# PAM8403_Amplifier_Board_R1.net
KiCad netlist of a schematic drawn in EAGLE
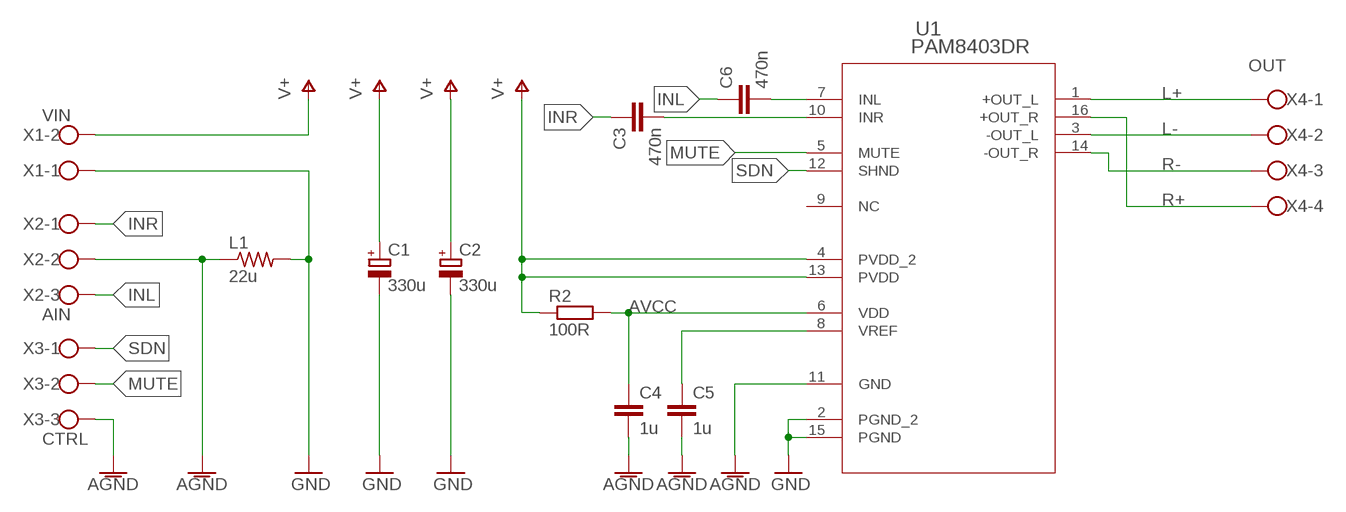
[diagram p0: schematic, sheet 1]

(export (version "E")
  (design (tool "Eeschema 10.0.6"))
  (components
    (comp (ref "C1")
      (value "330u")
      (footprint "eagle-import:E3,5-8")
      (libsource (lib "eagle-import") (part "CPOL-EUE3.5-8"))
    )
    (comp (ref "C2")
      (value "330u")
      (footprint "eagle-import:E3,5-8")
      (libsource (lib "eagle-import") (part "CPOL-EUE3.5-8"))
    )
    (comp (ref "C3")
      (value "470n")
      (footprint "eagle-import:C1206")
      (libsource (lib "eagle-import") (part "C-EUC1206"))
    )
    (comp (ref "C4")
      (value "1u")
      (footprint "eagle-import:C1206")
      (libsource (lib "eagle-import") (part "C-EUC1206"))
    )
    (comp (ref "C5")
      (value "1u")
      (footprint "eagle-import:C1206")
      (libsource (lib "eagle-import") (part "C-EUC1206"))
    )
    (comp (ref "C6")
      (value "470n")
      (footprint "eagle-import:C1206")
      (libsource (lib "eagle-import") (part "C-EUC1206"))
    )
    (comp (ref "L1")
      (value "22u")
      (footprint "eagle-import:R0805")
      (libsource (lib "eagle-import") (part "R-US_R0805"))
    )
    (comp (ref "R2")
      (value "100R")
      (footprint "eagle-import:R0603")
      (libsource (lib "eagle-import") (part "R-EU_R0603"))
    )
    (comp (ref "U1")
      (value "PAM8403DR")
      (footprint "eagle-import:SOIC_8403DR_DIO")
      (fields (field (name "COPYRIGHT") "Copyright (C) 2023 Ultra Librarian. All rights reserved."))
      (libsource (lib "eagle-import") (part "PAM8403DR"))
    )
    (comp (ref "X1")
      (value "VIN")
      (footprint "eagle-import:W237-102")
      (fields (field (name "MPN") "237-102"))
      (libsource (lib "eagle-import") (part "W237-102"))
    )
    (comp (ref "X2")
      (value "AIN")
      (footprint "eagle-import:W237-103")
      (fields (field (name "MPN") "237-103"))
      (libsource (lib "eagle-import") (part "W237-103"))
    )
    (comp (ref "X3")
      (value "CTRL")
      (footprint "eagle-import:W237-103")
      (fields (field (name "MPN") "237-103"))
      (libsource (lib "eagle-import") (part "W237-103"))
    )
    (comp (ref "X4")
      (value "OUT")
      (footprint "eagle-import:W237-4")
      (libsource (lib "eagle-import") (part "W237-4"))
    )
  )
  (nets
    (net (code "1") (name "/AVCC") (class "Default")
      (node (ref "C4") (pin "1") (pinfunction "1_1") (pintype "passive"))
      (node (ref "R2") (pin "2") (pinfunction "2_2") (pintype "passive"))
      (node (ref "U1") (pin "6") (pinfunction "VDD_6") (pintype "power_in"))
    )
    (net (code "2") (name "/L+") (class "Default")
      (node (ref "U1") (pin "1") (pinfunction "+OUT_L_1") (pintype "output"))
      (node (ref "X4") (pin "1") (pinfunction "KL_1") (pintype "passive"))
    )
    (net (code "3") (name "/L-") (class "Default")
      (node (ref "U1") (pin "3") (pinfunction "-OUT_L_3") (pintype "output"))
      (node (ref "X4") (pin "2") (pinfunction "KL_2") (pintype "passive"))
    )
    (net (code "4") (name "/R+") (class "Default")
      (node (ref "U1") (pin "16") (pinfunction "+OUT_R_16") (pintype "output"))
      (node (ref "X4") (pin "4") (pinfunction "KL_4") (pintype "passive"))
    )
    (net (code "5") (name "/R-") (class "Default")
      (node (ref "U1") (pin "14") (pinfunction "-OUT_R_14") (pintype "output"))
      (node (ref "X4") (pin "3") (pinfunction "KL_3") (pintype "passive"))
    )
    (net (code "6") (name "AGND") (class "Default")
      (node (ref "C4") (pin "2") (pinfunction "2_2") (pintype "passive"))
      (node (ref "C5") (pin "2") (pinfunction "2_2") (pintype "passive"))
      (node (ref "L1") (pin "1") (pinfunction "1_1") (pintype "passive"))
      (node (ref "U1") (pin "11") (pinfunction "GND_11") (pintype "passive"))
      (node (ref "X2") (pin "2") (pinfunction "KL_2") (pintype "passive"))
      (node (ref "X3") (pin "3") (pinfunction "KL_3") (pintype "passive"))
    )
    (net (code "7") (name "GND") (class "Default")
      (node (ref "C1") (pin "-") (pinfunction "-_-") (pintype "passive"))
      (node (ref "C2") (pin "-") (pinfunction "-_-") (pintype "passive"))
      (node (ref "L1") (pin "2") (pinfunction "2_2") (pintype "passive"))
      (node (ref "U1") (pin "15") (pinfunction "PGND_15") (pintype "passive"))
      (node (ref "U1") (pin "2") (pinfunction "PGND_2_2") (pintype "passive"))
      (node (ref "X1") (pin "1") (pinfunction "KL_1") (pintype "passive"))
    )
    (net (code "8") (name "INL") (class "Default")
      (node (ref "C6") (pin "1") (pinfunction "1_1") (pintype "passive"))
      (node (ref "X2") (pin "3") (pinfunction "KL_3") (pintype "passive"))
    )
    (net (code "9") (name "INR") (class "Default")
      (node (ref "C3") (pin "1") (pinfunction "1_1") (pintype "passive"))
      (node (ref "X2") (pin "1") (pinfunction "KL_1") (pintype "passive"))
    )
    (net (code "10") (name "MUTE") (class "Default")
      (node (ref "U1") (pin "5") (pinfunction "MUTE_5") (pintype "passive"))
      (node (ref "X3") (pin "2") (pinfunction "KL_2") (pintype "passive"))
    )
    (net (code "11") (name "Net-(U1-INL)") (class "Default")
      (node (ref "C6") (pin "2") (pinfunction "2_2") (pintype "passive"))
      (node (ref "U1") (pin "7") (pinfunction "INL_7") (pintype "passive"))
    )
    (net (code "12") (name "Net-(U1-INR)") (class "Default")
      (node (ref "C3") (pin "2") (pinfunction "2_2") (pintype "passive"))
      (node (ref "U1") (pin "10") (pinfunction "INR_10") (pintype "passive"))
    )
    (net (code "13") (name "Net-(U1-VREF)") (class "Default")
      (node (ref "C5") (pin "1") (pinfunction "1_1") (pintype "passive"))
      (node (ref "U1") (pin "8") (pinfunction "VREF_8") (pintype "power_in"))
    )
    (net (code "14") (name "SDN") (class "Default")
      (node (ref "U1") (pin "12") (pinfunction "SHND_12") (pintype "passive"))
      (node (ref "X3") (pin "1") (pinfunction "KL_1") (pintype "passive"))
    )
    (net (code "15") (name "V+") (class "Default")
      (node (ref "C1") (pin "+") (pinfunction "+_+") (pintype "passive"))
      (node (ref "C2") (pin "+") (pinfunction "+_+") (pintype "passive"))
      (node (ref "R2") (pin "1") (pinfunction "1_1") (pintype "passive"))
      (node (ref "U1") (pin "13") (pinfunction "PVDD_13") (pintype "power_in"))
      (node (ref "U1") (pin "4") (pinfunction "PVDD_2_4") (pintype "power_in"))
      (node (ref "X1") (pin "2") (pinfunction "KL_2") (pintype "passive"))
    )
    (net (code "16") (name "unconnected-(U1-NC-Pad9)") (class "Default")
      (node (ref "U1") (pin "9") (pinfunction "NC_9") (pintype "no_connect"))
    )
  )
)
